# Top.net
KiCad netlist of a schematic drawn in Altium Designer
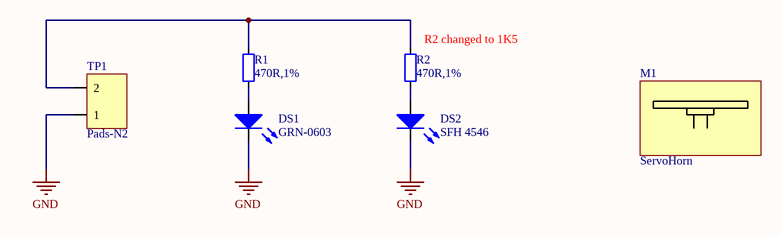
[diagram p0: Top.SchDoc]

(export (version "E")
  (design (tool "Eeschema 10.0.6"))
  (components
    (comp (ref "DS1")
      (value "GRN-0603")
      (footprint "LED_SML-LX0603")
      (description "LED GREEN CLEAR 0603 SMD")
      (fields
        (field (name "MANUFACTURER") "Dialight")
        (field (name "MANUFACTURER PART NUMBER") "5988081107F")
      )
      (libsource (lib "library") (part "LED_1"))
    )
    (comp (ref "DS2")
      (value "SFH 4546")
      (footprint "P375-504")
      (description "EMITTER IR 940NM 100MA RADIAL")
      (fields (field (name "MANUFACTURER") "Osram"))
      (libsource (lib "library") (part "LED_1"))
    )
    (comp (ref "M1")
      (value "ServoHorn")
      (footprint "SERVO_HORN")
      (libsource (lib "Common") (part "ServoHorn"))
    )
    (comp (ref "R1")
      (value "470R,1%")
      (footprint "RESC1608X06N_0603")
      (description "RES 470 OHM 1/10W 1% 0603 SMD")
      (fields (field (name "MANUFACTURER") "Rohm Semiconductor") (field (name "POWER") "0.1W"))
      (libsource (lib "library") (part "RESISTOR_1"))
    )
    (comp (ref "R2")
      (value "470R,1%")
      (footprint "RESC1608X06N_0603")
      (description "RES 470 OHM 1/10W 1% 0603 SMD")
      (fields (field (name "MANUFACTURER") "Rohm Semiconductor") (field (name "POWER") "0.1W"))
      (libsource (lib "library") (part "RESISTOR_1"))
    )
    (comp (ref "TP1") (value "Pads-N2") (footprint "PADS-N2") (libsource (lib "Common") (part "Pads-N2")))
  )
  (nets
    (net (code "1") (name "GND") (class "Default")
      (node (ref "DS1") (pin "1") (pinfunction "C_1") (pintype "passive"))
      (node (ref "DS2") (pin "1") (pinfunction "C_1") (pintype "passive"))
      (node (ref "TP1") (pin "1") (pinfunction "1_1") (pintype "passive"))
    )
    (net (code "2") (name "Net-(DS1-A)") (class "Default")
      (node (ref "DS1") (pin "2") (pinfunction "A_2") (pintype "passive"))
      (node (ref "R1") (pin "1") (pinfunction "1_1") (pintype "passive"))
    )
    (net (code "3") (name "Net-(DS2-A)") (class "Default")
      (node (ref "DS2") (pin "2") (pinfunction "A_2") (pintype "passive"))
      (node (ref "R2") (pin "1") (pinfunction "1_1") (pintype "passive"))
    )
    (net (code "4") (name "Net-(R1-Pad2)") (class "Default")
      (node (ref "R1") (pin "2") (pinfunction "2_2") (pintype "passive"))
      (node (ref "R2") (pin "2") (pinfunction "2_2") (pintype "passive"))
      (node (ref "TP1") (pin "2") (pinfunction "2_2") (pintype "passive"))
    )
  )
)
